# nano_shield.net
KiCad netlist of a schematic drawn in EAGLE
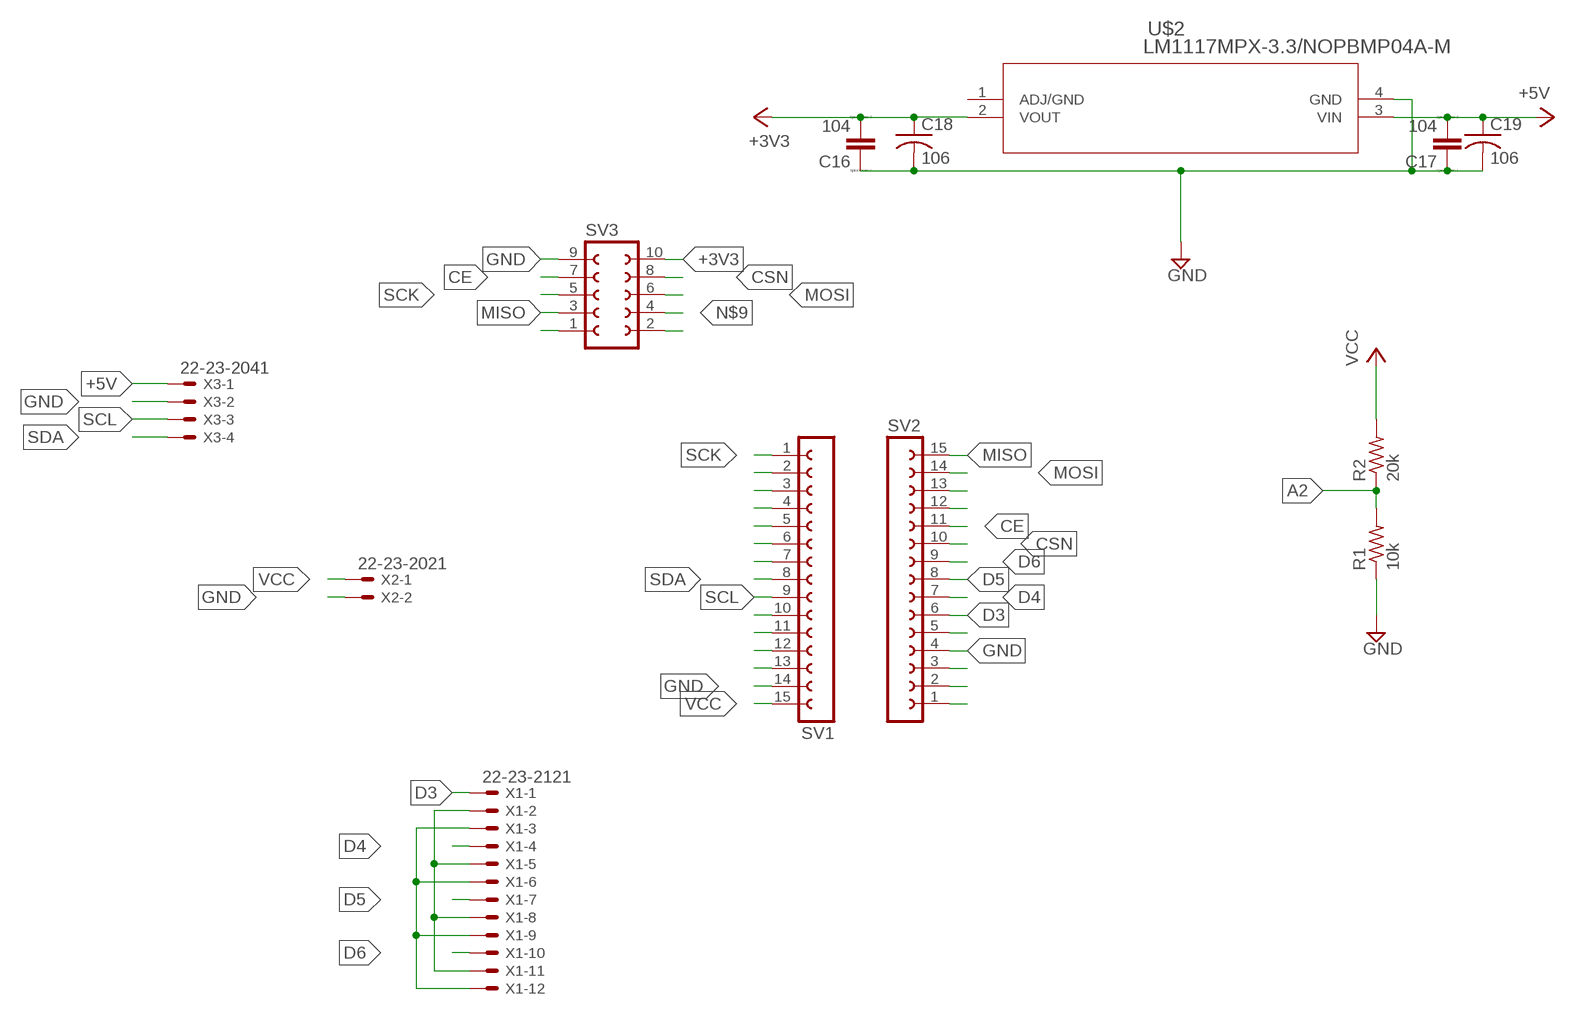
[diagram p0: schematic, sheet 1]

(export (version "E")
  (design (tool "Eeschema 10.0.6"))
  (components
    (comp (ref "C16")
      (value "104")
      (footprint "eagle-import:C0603")
      (libsource (lib "eagle-import") (part "CC0603"))
    )
    (comp (ref "C17")
      (value "104")
      (footprint "eagle-import:C0603")
      (libsource (lib "eagle-import") (part "CC0603"))
    )
    (comp (ref "C18")
      (value "106")
      (footprint "eagle-import:C0805")
      (libsource (lib "eagle-import") (part "C-USC0805"))
    )
    (comp (ref "C19")
      (value "106")
      (footprint "eagle-import:C0805")
      (libsource (lib "eagle-import") (part "C-USC0805"))
    )
    (comp (ref "R1")
      (value "10k")
      (footprint "eagle-import:R0603")
      (libsource (lib "eagle-import") (part "R-US_R0603"))
    )
    (comp (ref "R2")
      (value "20k")
      (footprint "eagle-import:R0603")
      (libsource (lib "eagle-import") (part "R-US_R0603"))
    )
    (comp (ref "SV1")
      (value "FE15-1")
      (footprint "eagle-import:FE15")
      (libsource (lib "eagle-import") (part "FE15-1"))
    )
    (comp (ref "SV2")
      (value "FE15-1")
      (footprint "eagle-import:FE15")
      (libsource (lib "eagle-import") (part "FE15-1"))
    )
    (comp (ref "SV3")
      (value "FE05-2")
      (footprint "eagle-import:FE05-2")
      (libsource (lib "eagle-import") (part "FE05-2"))
    )
    (comp (ref "U$2")
      (value "LM1117MPX-3.3/NOPBMP04A-M")
      (footprint "eagle-import:MP04A-M")
      (fields (field (name "MANUFACTURER_PART_NUMBER") "LM1117MPX3.3NOPB"))
      (libsource (lib "eagle-import") (part "LM1117MPX-3.3/NOPBMP04A-M"))
    )
    (comp (ref "X1")
      (value "22-23-2121")
      (footprint "eagle-import:22-23-2121")
      (fields (field (name "MF") "MOLEX"))
      (libsource (lib "eagle-import") (part "22-23-2121"))
    )
    (comp (ref "X2")
      (value "22-23-2021")
      (footprint "eagle-import:22-23-2021")
      (fields (field (name "MF") "MOLEX"))
      (libsource (lib "eagle-import") (part "22-23-2021"))
    )
    (comp (ref "X3")
      (value "22-23-2041")
      (footprint "eagle-import:22-23-2041")
      (fields (field (name "MF") "MOLEX"))
      (libsource (lib "eagle-import") (part "22-23-2041"))
    )
  )
  (nets
    (net (code "1") (name "+3V3") (class "Default")
      (node (ref "C16") (pin "2") (pinfunction "2_2") (pintype "passive"))
      (node (ref "C18") (pin "1") (pinfunction "1_1") (pintype "passive"))
      (node (ref "SV3") (pin "10") (pinfunction "10_10") (pintype "passive"))
      (node (ref "U$2") (pin "2") (pinfunction "VOUT_2") (pintype "output"))
    )
    (net (code "2") (name "+5V") (class "Default")
      (node (ref "C17") (pin "2") (pinfunction "2_2") (pintype "passive"))
      (node (ref "C19") (pin "1") (pinfunction "1_1") (pintype "passive"))
      (node (ref "U$2") (pin "3") (pinfunction "VIN_3") (pintype "input"))
      (node (ref "X1") (pin "11") (pinfunction "S_11") (pintype "passive"))
      (node (ref "X1") (pin "2") (pinfunction "S_2") (pintype "passive"))
      (node (ref "X1") (pin "5") (pinfunction "S_5") (pintype "passive"))
      (node (ref "X1") (pin "8") (pinfunction "S_8") (pintype "passive"))
      (node (ref "X3") (pin "1") (pinfunction "S_1") (pintype "passive"))
    )
    (net (code "3") (name "A2") (class "Default")
      (node (ref "R1") (pin "2") (pinfunction "2_2") (pintype "passive"))
      (node (ref "R2") (pin "1") (pinfunction "1_1") (pintype "passive"))
      (node (ref "SV1") (pin "6") (pinfunction "6_6") (pintype "passive"))
    )
    (net (code "4") (name "CE") (class "Default")
      (node (ref "SV2") (pin "11") (pinfunction "11_11") (pintype "passive"))
      (node (ref "SV3") (pin "7") (pinfunction "7_7") (pintype "passive"))
    )
    (net (code "5") (name "CSN") (class "Default")
      (node (ref "SV2") (pin "10") (pinfunction "10_10") (pintype "passive"))
      (node (ref "SV3") (pin "8") (pinfunction "8_8") (pintype "passive"))
    )
    (net (code "6") (name "D3") (class "Default")
      (node (ref "SV2") (pin "6") (pinfunction "6_6") (pintype "passive"))
      (node (ref "X1") (pin "1") (pinfunction "S_1") (pintype "passive"))
    )
    (net (code "7") (name "D4") (class "Default")
      (node (ref "SV2") (pin "7") (pinfunction "7_7") (pintype "passive"))
      (node (ref "X1") (pin "4") (pinfunction "S_4") (pintype "passive"))
    )
    (net (code "8") (name "D5") (class "Default")
      (node (ref "SV2") (pin "8") (pinfunction "8_8") (pintype "passive"))
      (node (ref "X1") (pin "7") (pinfunction "S_7") (pintype "passive"))
    )
    (net (code "9") (name "D6") (class "Default")
      (node (ref "SV2") (pin "9") (pinfunction "9_9") (pintype "passive"))
      (node (ref "X1") (pin "10") (pinfunction "S_10") (pintype "passive"))
    )
    (net (code "10") (name "GND") (class "Default")
      (node (ref "C16") (pin "1") (pinfunction "1_1") (pintype "passive"))
      (node (ref "C17") (pin "1") (pinfunction "1_1") (pintype "passive"))
      (node (ref "C18") (pin "2") (pinfunction "2_2") (pintype "passive"))
      (node (ref "C19") (pin "2") (pinfunction "2_2") (pintype "passive"))
      (node (ref "R1") (pin "1") (pinfunction "1_1") (pintype "passive"))
      (node (ref "SV1") (pin "14") (pinfunction "14_14") (pintype "passive"))
      (node (ref "SV2") (pin "4") (pinfunction "4_4") (pintype "passive"))
      (node (ref "SV3") (pin "9") (pinfunction "9_9") (pintype "passive"))
      (node (ref "U$2") (pin "4") (pinfunction "GND_4") (pintype "power_in"))
      (node (ref "X1") (pin "12") (pinfunction "S_12") (pintype "passive"))
      (node (ref "X1") (pin "3") (pinfunction "S_3") (pintype "passive"))
      (node (ref "X1") (pin "6") (pinfunction "S_6") (pintype "passive"))
      (node (ref "X1") (pin "9") (pinfunction "S_9") (pintype "passive"))
      (node (ref "X2") (pin "2") (pinfunction "S_2") (pintype "passive"))
      (node (ref "X3") (pin "2") (pinfunction "S_2") (pintype "passive"))
    )
    (net (code "11") (name "MISO") (class "Default")
      (node (ref "SV2") (pin "15") (pinfunction "15_15") (pintype "passive"))
      (node (ref "SV3") (pin "3") (pinfunction "3_3") (pintype "passive"))
    )
    (net (code "12") (name "MOSI") (class "Default")
      (node (ref "SV2") (pin "14") (pinfunction "14_14") (pintype "passive"))
      (node (ref "SV3") (pin "6") (pinfunction "6_6") (pintype "passive"))
    )
    (net (code "13") (name "N$9") (class "Default")
      (node (ref "SV3") (pin "4") (pinfunction "4_4") (pintype "passive"))
    )
    (net (code "14") (name "SCK") (class "Default")
      (node (ref "SV1") (pin "1") (pinfunction "1_1") (pintype "passive"))
      (node (ref "SV3") (pin "5") (pinfunction "5_5") (pintype "passive"))
    )
    (net (code "15") (name "SCL") (class "Default")
      (node (ref "SV1") (pin "9") (pinfunction "9_9") (pintype "passive"))
      (node (ref "X3") (pin "3") (pinfunction "S_3") (pintype "passive"))
    )
    (net (code "16") (name "SDA") (class "Default")
      (node (ref "SV1") (pin "8") (pinfunction "8_8") (pintype "passive"))
      (node (ref "X3") (pin "4") (pinfunction "S_4") (pintype "passive"))
    )
    (net (code "17") (name "VCC") (class "Default")
      (node (ref "R2") (pin "2") (pinfunction "2_2") (pintype "passive"))
      (node (ref "SV1") (pin "15") (pinfunction "15_15") (pintype "passive"))
      (node (ref "X2") (pin "1") (pinfunction "S_1") (pintype "passive"))
    )
    (net (code "18") (name "unconnected-(SV1-Pad2)") (class "Default")
      (node (ref "SV1") (pin "2") (pinfunction "2_2") (pintype "passive"))
    )
    (net (code "19") (name "unconnected-(SV1-Pad3)") (class "Default")
      (node (ref "SV1") (pin "3") (pinfunction "3_3") (pintype "passive"))
    )
    (net (code "20") (name "unconnected-(SV1-Pad4)") (class "Default")
      (node (ref "SV1") (pin "4") (pinfunction "4_4") (pintype "passive"))
    )
    (net (code "21") (name "unconnected-(SV1-Pad5)") (class "Default")
      (node (ref "SV1") (pin "5") (pinfunction "5_5") (pintype "passive"))
    )
    (net (code "22") (name "unconnected-(SV1-Pad7)") (class "Default")
      (node (ref "SV1") (pin "7") (pinfunction "7_7") (pintype "passive"))
    )
    (net (code "23") (name "unconnected-(SV1-Pad10)") (class "Default")
      (node (ref "SV1") (pin "10") (pinfunction "10_10") (pintype "passive"))
    )
    (net (code "24") (name "unconnected-(SV1-Pad11)") (class "Default")
      (node (ref "SV1") (pin "11") (pinfunction "11_11") (pintype "passive"))
    )
    (net (code "25") (name "unconnected-(SV1-Pad12)") (class "Default")
      (node (ref "SV1") (pin "12") (pinfunction "12_12") (pintype "passive"))
    )
    (net (code "26") (name "unconnected-(SV1-Pad13)") (class "Default")
      (node (ref "SV1") (pin "13") (pinfunction "13_13") (pintype "passive"))
    )
    (net (code "27") (name "unconnected-(SV2-Pad1)") (class "Default")
      (node (ref "SV2") (pin "1") (pinfunction "1_1") (pintype "passive"))
    )
    (net (code "28") (name "unconnected-(SV2-Pad2)") (class "Default")
      (node (ref "SV2") (pin "2") (pinfunction "2_2") (pintype "passive"))
    )
    (net (code "29") (name "unconnected-(SV2-Pad3)") (class "Default")
      (node (ref "SV2") (pin "3") (pinfunction "3_3") (pintype "passive"))
    )
    (net (code "30") (name "unconnected-(SV2-Pad5)") (class "Default")
      (node (ref "SV2") (pin "5") (pinfunction "5_5") (pintype "passive"))
    )
    (net (code "31") (name "unconnected-(SV2-Pad12)") (class "Default")
      (node (ref "SV2") (pin "12") (pinfunction "12_12") (pintype "passive"))
    )
    (net (code "32") (name "unconnected-(SV2-Pad13)") (class "Default")
      (node (ref "SV2") (pin "13") (pinfunction "13_13") (pintype "passive"))
    )
    (net (code "33") (name "unconnected-(SV3-Pad1)") (class "Default")
      (node (ref "SV3") (pin "1") (pinfunction "1_1") (pintype "passive"))
    )
    (net (code "34") (name "unconnected-(SV3-Pad2)") (class "Default")
      (node (ref "SV3") (pin "2") (pinfunction "2_2") (pintype "passive"))
    )
    (net (code "35") (name "unconnected-(U$2-ADJ{slash}GND-Pad1)") (class "Default")
      (node (ref "U$2") (pin "1") (pinfunction "ADJ/GND_1") (pintype "passive"))
    )
  )
)
